# quasi_nano_led_4wire.net
KiCad netlist of a schematic drawn in EAGLE
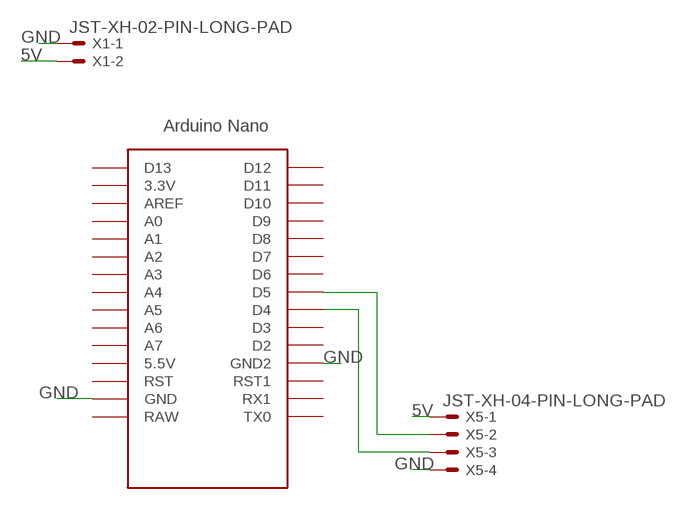
[diagram p0: schematic, sheet 1]

(export (version "E")
  (design (tool "Eeschema 10.0.6"))
  (components
    (comp (ref "U$1")
      (value "NANO")
      (footprint "eagle-import:NANO")
      (libsource (lib "eagle-import") (part "NANO"))
    )
    (comp (ref "X1")
      (value "JST-XH-02-PIN-LONG-PAD")
      (footprint "eagle-import:JST-XH-02-PACKAGE-LONG-PAD")
      (libsource (lib "eagle-import") (part "JST-XH-02-PIN-LONG-PAD"))
    )
    (comp (ref "X5")
      (value "JST-XH-04-PIN-LONG-PAD")
      (footprint "eagle-import:JST-XH-04-PACKAGE-LONG-PAD")
      (libsource (lib "eagle-import") (part "JST-XH-04-PIN-LONG-PAD"))
    )
  )
  (nets
    (net (code "1") (name "/5V") (class "Default")
      (node (ref "X1") (pin "2") (pinfunction "S_2") (pintype "passive"))
      (node (ref "X5") (pin "1") (pinfunction "S_1") (pintype "passive"))
    )
    (net (code "2") (name "/GND") (class "Default")
      (node (ref "U$1") (pin "GND") (pinfunction "GND_GND") (pintype "bidirectional"))
      (node (ref "U$1") (pin "GND1") (pinfunction "GND2_GND1") (pintype "bidirectional"))
      (node (ref "X1") (pin "1") (pinfunction "S_1") (pintype "passive"))
      (node (ref "X5") (pin "4") (pinfunction "S_4") (pintype "passive"))
    )
    (net (code "3") (name "Net-(X5B-S)") (class "Default")
      (node (ref "U$1") (pin "D5") (pinfunction "D5_D5") (pintype "bidirectional"))
      (node (ref "X5") (pin "2") (pinfunction "S_2") (pintype "passive"))
    )
    (net (code "4") (name "Net-(X5C-S)") (class "Default")
      (node (ref "U$1") (pin "D4") (pinfunction "D4_D4") (pintype "bidirectional"))
      (node (ref "X5") (pin "3") (pinfunction "S_3") (pintype "passive"))
    )
    (net (code "5") (name "unconnected-(U$1-5.5V-Pad5V)") (class "Default")
      (node (ref "U$1") (pin "5V") (pinfunction "5.5V_5V") (pintype "bidirectional"))
    )
    (net (code "6") (name "unconnected-(U$1-Pad3.3V)") (class "Default")
      (node (ref "U$1") (pin "3.3V") (pinfunction "3.3V_3.3V") (pintype "bidirectional"))
    )
    (net (code "7") (name "unconnected-(U$1-PadA0)") (class "Default")
      (node (ref "U$1") (pin "A0") (pinfunction "A0_A0") (pintype "bidirectional"))
    )
    (net (code "8") (name "unconnected-(U$1-PadA1)") (class "Default")
      (node (ref "U$1") (pin "A1") (pinfunction "A1_A1") (pintype "bidirectional"))
    )
    (net (code "9") (name "unconnected-(U$1-PadA2)") (class "Default")
      (node (ref "U$1") (pin "A2") (pinfunction "A2_A2") (pintype "bidirectional"))
    )
    (net (code "10") (name "unconnected-(U$1-PadA3)") (class "Default")
      (node (ref "U$1") (pin "A3") (pinfunction "A3_A3") (pintype "bidirectional"))
    )
    (net (code "11") (name "unconnected-(U$1-PadA4)") (class "Default")
      (node (ref "U$1") (pin "A4") (pinfunction "A4_A4") (pintype "bidirectional"))
    )
    (net (code "12") (name "unconnected-(U$1-PadA5)") (class "Default")
      (node (ref "U$1") (pin "A5") (pinfunction "A5_A5") (pintype "bidirectional"))
    )
    (net (code "13") (name "unconnected-(U$1-PadA6)") (class "Default")
      (node (ref "U$1") (pin "A6") (pinfunction "A6_A6") (pintype "bidirectional"))
    )
    (net (code "14") (name "unconnected-(U$1-PadA7)") (class "Default")
      (node (ref "U$1") (pin "A7") (pinfunction "A7_A7") (pintype "bidirectional"))
    )
    (net (code "15") (name "unconnected-(U$1-PadAREF)") (class "Default")
      (node (ref "U$1") (pin "AREF") (pinfunction "AREF_AREF") (pintype "bidirectional"))
    )
    (net (code "16") (name "unconnected-(U$1-PadD2)") (class "Default")
      (node (ref "U$1") (pin "D2") (pinfunction "D2_D2") (pintype "bidirectional"))
    )
    (net (code "17") (name "unconnected-(U$1-PadD3)") (class "Default")
      (node (ref "U$1") (pin "D3") (pinfunction "D3_D3") (pintype "bidirectional"))
    )
    (net (code "18") (name "unconnected-(U$1-PadD6)") (class "Default")
      (node (ref "U$1") (pin "D6") (pinfunction "D6_D6") (pintype "bidirectional"))
    )
    (net (code "19") (name "unconnected-(U$1-PadD7)") (class "Default")
      (node (ref "U$1") (pin "D7") (pinfunction "D7_D7") (pintype "bidirectional"))
    )
    (net (code "20") (name "unconnected-(U$1-PadD8)") (class "Default")
      (node (ref "U$1") (pin "D8") (pinfunction "D8_D8") (pintype "bidirectional"))
    )
    (net (code "21") (name "unconnected-(U$1-PadD9)") (class "Default")
      (node (ref "U$1") (pin "D9") (pinfunction "D9_D9") (pintype "bidirectional"))
    )
    (net (code "22") (name "unconnected-(U$1-PadD10)") (class "Default")
      (node (ref "U$1") (pin "D10") (pinfunction "D10_D10") (pintype "bidirectional"))
    )
    (net (code "23") (name "unconnected-(U$1-PadD11)") (class "Default")
      (node (ref "U$1") (pin "D11") (pinfunction "D11_D11") (pintype "bidirectional"))
    )
    (net (code "24") (name "unconnected-(U$1-PadD12)") (class "Default")
      (node (ref "U$1") (pin "D12") (pinfunction "D12_D12") (pintype "bidirectional"))
    )
    (net (code "25") (name "unconnected-(U$1-PadD13)") (class "Default")
      (node (ref "U$1") (pin "D13") (pinfunction "D13_D13") (pintype "bidirectional"))
    )
    (net (code "26") (name "unconnected-(U$1-PadICSP1)") (class "Default")
      (node (ref "U$1") (pin "ICSP1") (pinfunction "ICSP1_ICSP1") (pintype "bidirectional"))
    )
    (net (code "27") (name "unconnected-(U$1-PadICSP2)") (class "Default")
      (node (ref "U$1") (pin "ICSP2") (pinfunction "ICSP2_ICSP2") (pintype "bidirectional"))
    )
    (net (code "28") (name "unconnected-(U$1-PadICSP3)") (class "Default")
      (node (ref "U$1") (pin "ICSP3") (pinfunction "ICSP3_ICSP3") (pintype "bidirectional"))
    )
    (net (code "29") (name "unconnected-(U$1-PadICSP4)") (class "Default")
      (node (ref "U$1") (pin "ICSP4") (pinfunction "ICSP4_ICSP4") (pintype "bidirectional"))
    )
    (net (code "30") (name "unconnected-(U$1-PadICSP5)") (class "Default")
      (node (ref "U$1") (pin "ICSP5") (pinfunction "ICSP5_ICSP5") (pintype "bidirectional"))
    )
    (net (code "31") (name "unconnected-(U$1-PadICSP6)") (class "Default")
      (node (ref "U$1") (pin "ICSP6") (pinfunction "ICSP6_ICSP6") (pintype "bidirectional"))
    )
    (net (code "32") (name "unconnected-(U$1-PadRAW)") (class "Default")
      (node (ref "U$1") (pin "RAW") (pinfunction "RAW_RAW") (pintype "bidirectional"))
    )
    (net (code "33") (name "unconnected-(U$1-PadRST)") (class "Default")
      (node (ref "U$1") (pin "RST") (pinfunction "RST_RST") (pintype "bidirectional"))
    )
    (net (code "34") (name "unconnected-(U$1-PadRST1)") (class "Default")
      (node (ref "U$1") (pin "RST1") (pinfunction "RST1_RST1") (pintype "bidirectional"))
    )
    (net (code "35") (name "unconnected-(U$1-PadRX1)") (class "Default")
      (node (ref "U$1") (pin "RX1") (pinfunction "RX1_RX1") (pintype "bidirectional"))
    )
    (net (code "36") (name "unconnected-(U$1-PadTX0)") (class "Default")
      (node (ref "U$1") (pin "TX0") (pinfunction "TX0_TX0") (pintype "bidirectional"))
    )
  )
)
